# debugger.net
KiCad netlist of a schematic drawn in Altium Designer
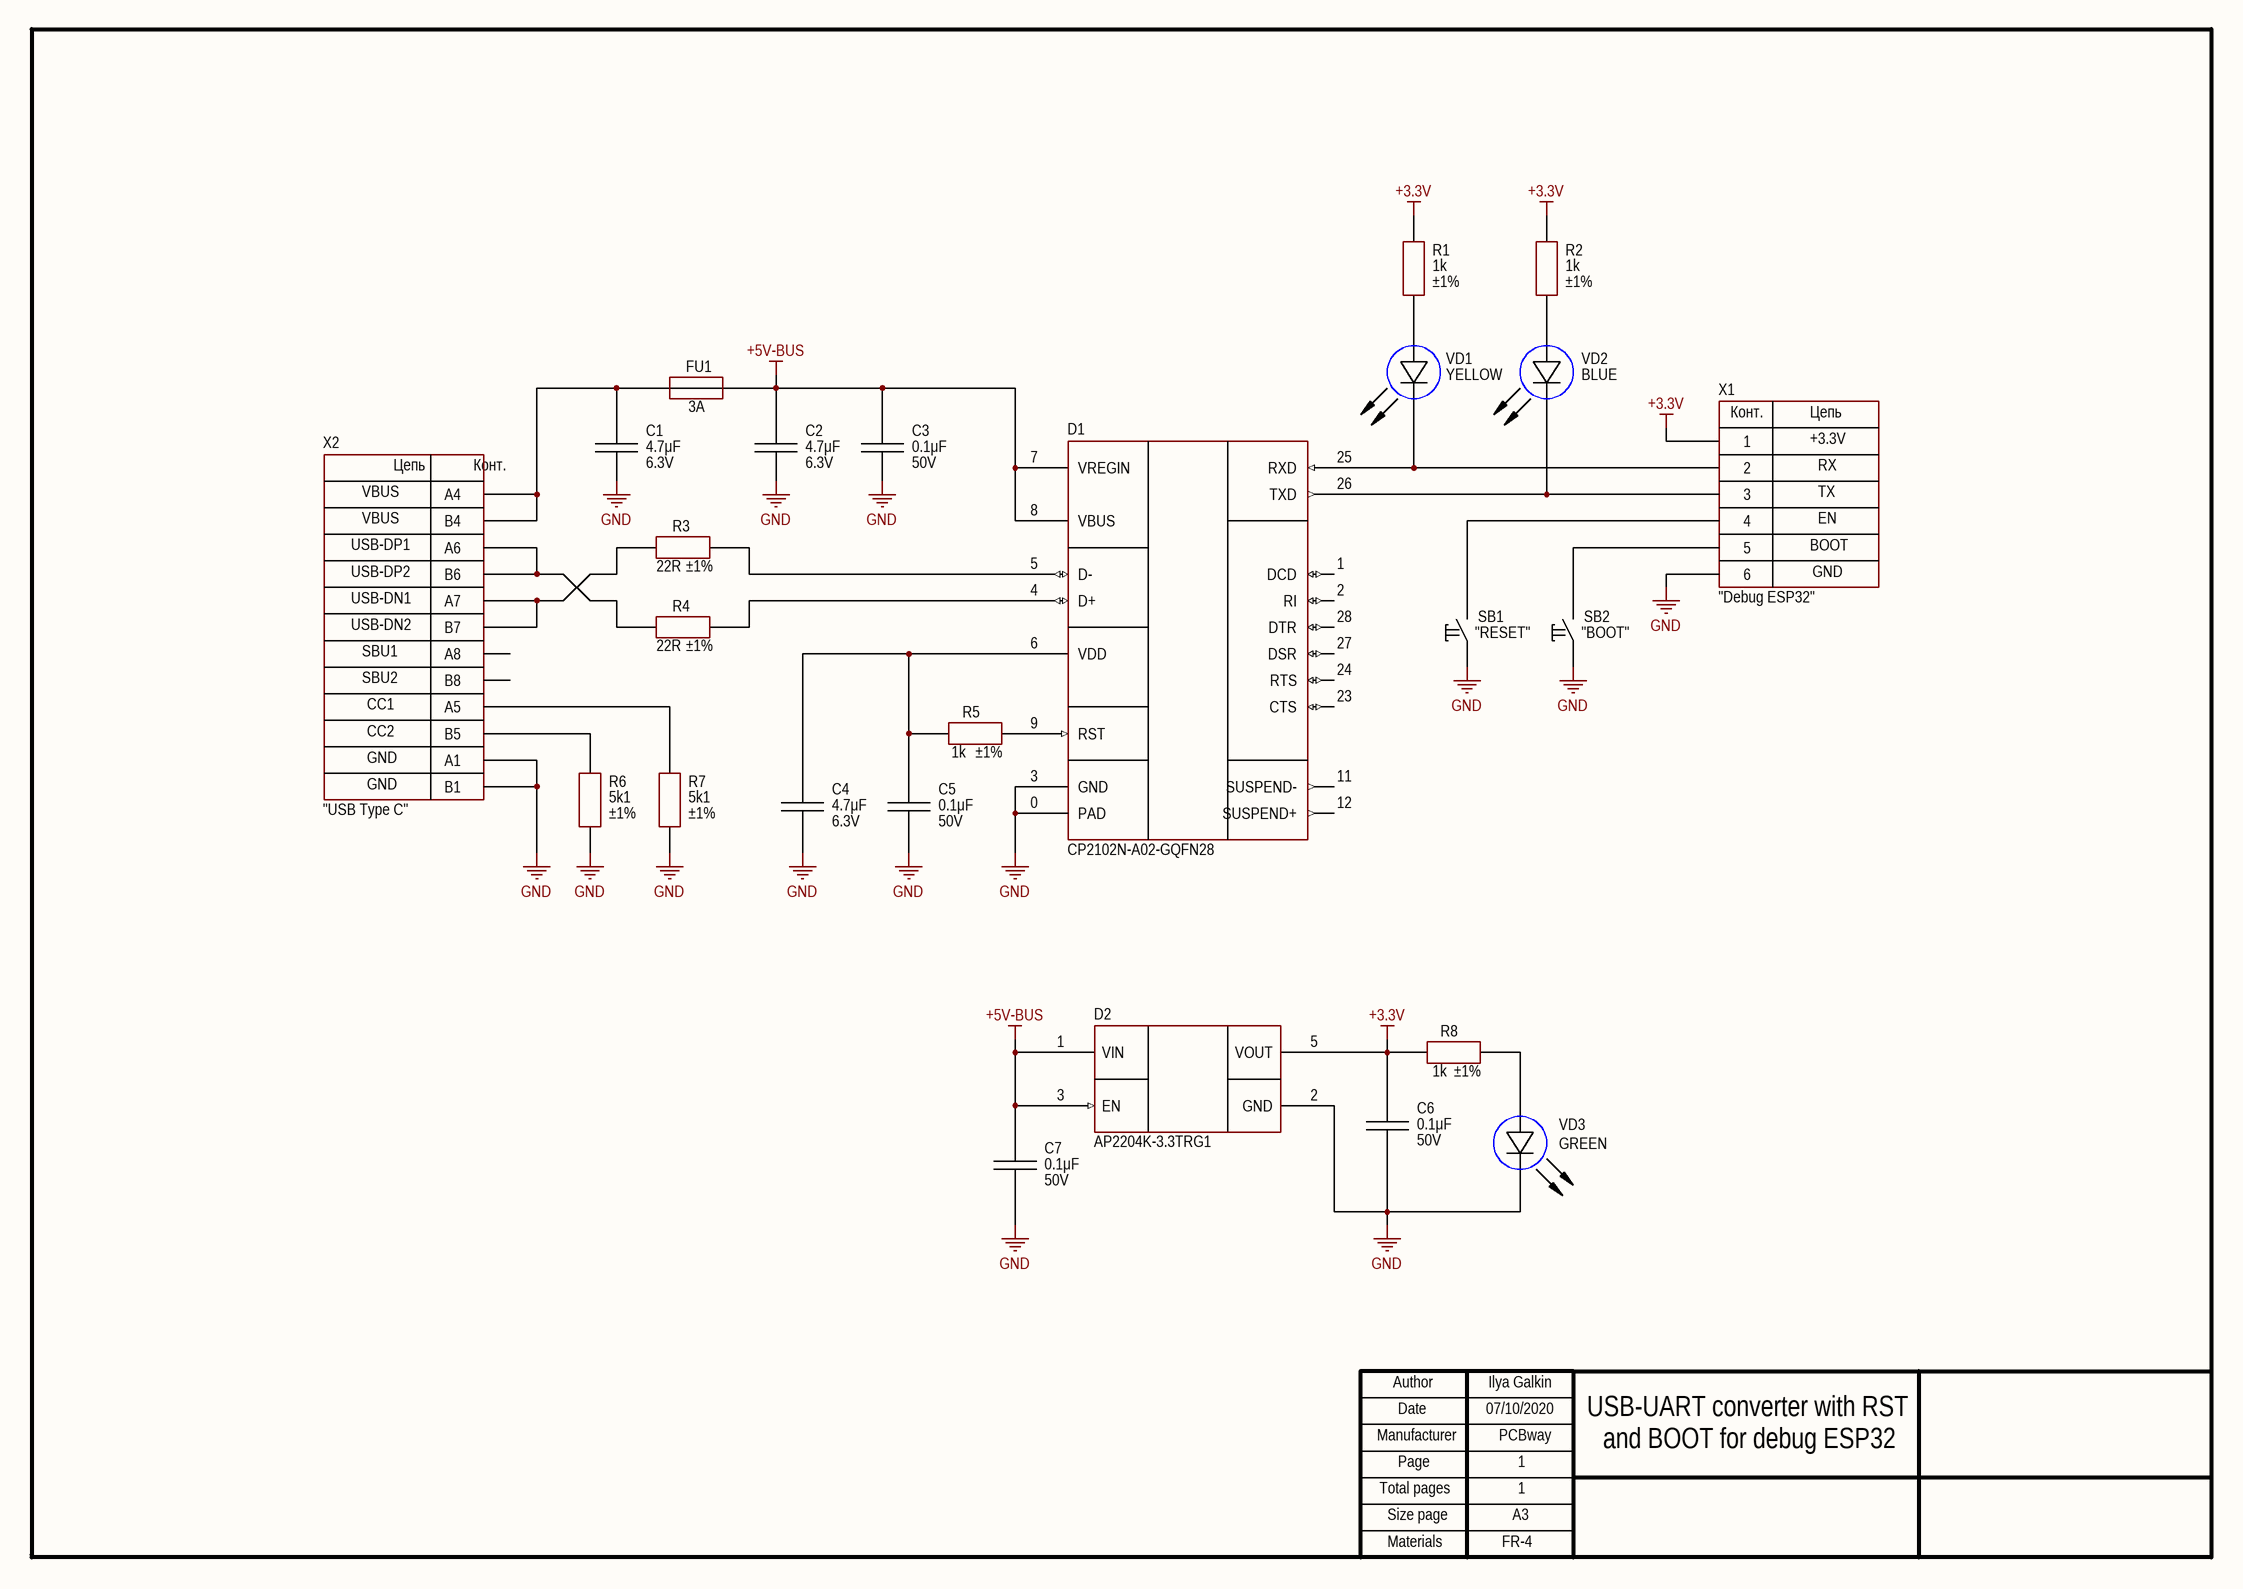
[diagram p0: debugger.SchDoc]

(export (version "E")
  (design (tool "Eeschema 10.0.6"))
  (components
    (comp (ref "C1")
      (value "4.7μF")
      (footprint "CAP: 0603")
      (fields
        (field (name "MANUFACTURER") "Samsung")
        (field (name "PARTNUMBER") "CL10B475KQ8NQNC")
        (field (name "VALUEMANUFACTURERPARTNUMBER") "Ceramic capacitor, 4.7μF, X7R, ±10%, 6.3V, 0603, -55...+125°C")
        (field (name "VOLTAGE") "6.3V")
      )
      (libsource (lib "capacitor") (part "Ceramic_0603"))
    )
    (comp (ref "C2")
      (value "4.7μF")
      (footprint "CAP: 0603")
      (fields
        (field (name "MANUFACTURER") "Samsung")
        (field (name "PARTNUMBER") "CL10B475KQ8NQNC")
        (field (name "VALUEMANUFACTURERPARTNUMBER") "Ceramic capacitor, 4.7μF, X7R, ±10%, 6.3V, 0603, -55...+125°C")
        (field (name "VOLTAGE") "6.3V")
      )
      (libsource (lib "capacitor") (part "Ceramic_0603"))
    )
    (comp (ref "C3")
      (value "0.1μF")
      (footprint "CAP: 0603")
      (fields
        (field (name "MANUFACTURER") "Samsung")
        (field (name "PARTNUMBER") "CL10B104KB8NNNL")
        (field (name "VALUEMANUFACTURERPARTNUMBER") "Ceramic capacitor, 0.1μF, X7R, ±10%, 50V, 0603, -55...+125°C")
        (field (name "VOLTAGE") "50V")
      )
      (libsource (lib "capacitor") (part "Ceramic_0603"))
    )
    (comp (ref "C4")
      (value "4.7μF")
      (footprint "CAP: 0603")
      (fields
        (field (name "MANUFACTURER") "Samsung")
        (field (name "PARTNUMBER") "CL10B475KQ8NQNC")
        (field (name "VALUEMANUFACTURERPARTNUMBER") "Ceramic capacitor, 4.7μF, X7R, ±10%, 6.3V, 0603, -55...+125°C")
        (field (name "VOLTAGE") "6.3V")
      )
      (libsource (lib "capacitor") (part "Ceramic_0603"))
    )
    (comp (ref "C5")
      (value "0.1μF")
      (footprint "CAP: 0603")
      (fields
        (field (name "MANUFACTURER") "Samsung")
        (field (name "PARTNUMBER") "CL10B104KB8NNNL")
        (field (name "VALUEMANUFACTURERPARTNUMBER") "Ceramic capacitor, 0.1μF, X7R, ±10%, 50V, 0603, -55...+125°C")
        (field (name "VOLTAGE") "50V")
      )
      (libsource (lib "capacitor") (part "Ceramic_0603"))
    )
    (comp (ref "C6")
      (value "0.1μF")
      (footprint "CAP: 0603")
      (fields
        (field (name "MANUFACTURER") "Samsung")
        (field (name "PARTNUMBER") "CL10B104KB8NNNL")
        (field (name "VALUEMANUFACTURERPARTNUMBER") "Ceramic capacitor, 0.1μF, X7R, ±10%, 50V, 0603, -55...+125°C")
        (field (name "VOLTAGE") "50V")
      )
      (libsource (lib "capacitor") (part "Ceramic_0603"))
    )
    (comp (ref "C7")
      (value "0.1μF")
      (footprint "CAP: 0603")
      (fields
        (field (name "MANUFACTURER") "Samsung")
        (field (name "PARTNUMBER") "CL10B104KB8NNNL")
        (field (name "VALUEMANUFACTURERPARTNUMBER") "Ceramic capacitor, 0.1μF, X7R, ±10%, 50V, 0603, -55...+125°C")
        (field (name "VOLTAGE") "50V")
      )
      (libsource (lib "capacitor") (part "Ceramic_0603"))
    )
    (comp (ref "D1")
      (value "~")
      (footprint "28-QFN (5x5)")
      (description "USB-to-UART")
      (fields
        (field (name "MANUFACTURER") "Silicon Labs")
        (field (name "VALUEMANUFACTURERPARTNUMBER") "IC usb-to-uart bridge, USB2.0, 3...3.6V, -40...+85°C, 28-VFQFN")
        (field (name "PARTNUMBER") "CP2102N-A02-GQFN28")
      )
      (libsource (lib "ic-interface") (part "CP2102N"))
    )
    (comp (ref "D2")
      (value "~")
      (footprint "SOT23-5")
      (description "Linear voltage regulator")
      (fields
        (field (name "MANUFACTURER") "Diodes Incorporated")
        (field (name "VALUEMANUFACTURERPARTNUMBER") "Linear voltage regulator, input 4...24V, 0.5V, output 3.3V, 0.15A, -40...+85°C, SOT23-6")
        (field (name "PARTNUMBER") "AP2204K-3.3TRG1")
      )
      (libsource (lib "ic-power-supply") (part "AP2204K-3.3TRG1"))
    )
    (comp (ref "FU1")
      (value "~")
      (footprint "FUSE: 1206")
      (fields
        (field (name "MANUFACTURER") "Panasonic")
        (field (name "VALUEMANUFACTURERPARTNUMBER") "Electromechanics relay, 32VDC, 3A, 1206 case, ")
        (field (name "PARTNUMBER") "ERB-RG3R00V")
        (field (name "MAXCURRENT") "3A")
      )
      (libsource (lib "electromechanics") (part "Fuse"))
    )
    (comp (ref "R1")
      (value "1k")
      (footprint "RES: 0603")
      (fields
        (field (name "MANUFACTURER") "Yageo")
        (field (name "PARTNUMBER") "RC0603FR-071KL")
        (field (name "VALUEMANUFACTURERPARTNUMBER") "Resistor film, 1k, ±1%, 0603, 0.1W, -55...+125°C")
        (field (name "TOLERANCE") "±1%")
      )
      (libsource (lib "") (part "Resistor_0603_1"))
    )
    (comp (ref "R2")
      (value "1k")
      (footprint "RES: 0603")
      (fields
        (field (name "MANUFACTURER") "Yageo")
        (field (name "PARTNUMBER") "RC0603FR-071KL")
        (field (name "VALUEMANUFACTURERPARTNUMBER") "Resistor film, 1k, ±1%, 0603, 0.1W, -55...+125°C")
        (field (name "TOLERANCE") "±1%")
      )
      (libsource (lib "") (part "Resistor_0603_1"))
    )
    (comp (ref "R3")
      (value "22R")
      (footprint "RES: 0603")
      (fields
        (field (name "MANUFACTURER") "Yageo")
        (field (name "PARTNUMBER") "RC0603FR-0722RL")
        (field (name "VALUEMANUFACTURERPARTNUMBER") "Resistor film, 22R, ±1%, 0603, 0.1W, -55...+125°C")
        (field (name "TOLERANCE") "±1%")
      )
      (libsource (lib "Resistor") (part "Resistor_0603"))
    )
    (comp (ref "R4")
      (value "22R")
      (footprint "RES: 0603")
      (fields
        (field (name "MANUFACTURER") "Yageo")
        (field (name "PARTNUMBER") "RC0603FR-0722RL")
        (field (name "VALUEMANUFACTURERPARTNUMBER") "Resistor film, 22R, ±1%, 0603, 0.1W, -55...+125°C")
        (field (name "TOLERANCE") "±1%")
      )
      (libsource (lib "Resistor") (part "Resistor_0603"))
    )
    (comp (ref "R5")
      (value "1k")
      (footprint "RES: 0603")
      (fields
        (field (name "MANUFACTURER") "Yageo")
        (field (name "PARTNUMBER") "RC0603FR-071KL")
        (field (name "VALUEMANUFACTURERPARTNUMBER") "Resistor film, 1k, ±1%, 0603, 0.1W, -55...+125°C")
        (field (name "TOLERANCE") "±1%")
      )
      (libsource (lib "resistor") (part "Resistor_0603"))
    )
    (comp (ref "R6")
      (value "5k1")
      (footprint "RES: 0603")
      (fields
        (field (name "MANUFACTURER") "Yageo")
        (field (name "PARTNUMBER") "RC0603FR-075K1L")
        (field (name "VALUEMANUFACTURERPARTNUMBER") "Resistor film, 5k1, ±1%, 0603, 0.1W, -55...+125°C")
        (field (name "TOLERANCE") "±1%")
      )
      (libsource (lib "") (part "Resistor_0603_1"))
    )
    (comp (ref "R7")
      (value "5k1")
      (footprint "RES: 0603")
      (fields
        (field (name "MANUFACTURER") "Yageo")
        (field (name "PARTNUMBER") "RC0603FR-075K1L")
        (field (name "VALUEMANUFACTURERPARTNUMBER") "Resistor film, 5k1, ±1%, 0603, 0.1W, -55...+125°C")
        (field (name "TOLERANCE") "±1%")
      )
      (libsource (lib "") (part "Resistor_0603_1"))
    )
    (comp (ref "R8")
      (value "1k")
      (footprint "RES: 0603")
      (fields
        (field (name "MANUFACTURER") "Yageo")
        (field (name "PARTNUMBER") "RC0603FR-071KL")
        (field (name "VALUEMANUFACTURERPARTNUMBER") "Resistor film, 1k, ±1%, 0603, 0.1W, -55...+125°C")
        (field (name "TOLERANCE") "±1%")
      )
      (libsource (lib "") (part "Resistor_0603_2"))
    )
    (comp (ref "SB1")
      (value "~")
      (footprint "BUT: 6x3.5 SMD")
      (fields
        (field (name "MANUFACTURER") "TE Connectivity")
        (field (name "VALUEMANUFACTURERPARTNUMBER") "Tactile button, 6x6mm")
        (field (name "PARTNUMBER") "FSM2JSMAATR")
        (field (name "COMMENTTEXT") "\"RESET\"")
      )
      (libsource (lib "electromechanics") (part "Button_tactile"))
    )
    (comp (ref "SB2")
      (value "~")
      (footprint "BUT: 6x3.5 SMD")
      (fields
        (field (name "MANUFACTURER") "TE Connectivity")
        (field (name "VALUEMANUFACTURERPARTNUMBER") "Tactile button, 6x3.5mm")
        (field (name "PARTNUMBER") "FSM2JSMAATR")
        (field (name "COMMENTTEXT") "\"BOOT\"")
      )
      (libsource (lib "electromechanics") (part "Button_tactile"))
    )
    (comp (ref "VD1")
      (value "~")
      (footprint "LED: 0603Y")
      (fields
        (field (name "MANUFACTURER") "Wurth")
        (field (name "VALUEMANUFACTURERPARTNUMBER") "LED, 20mA, 2V, 0603, -55...+150°C")
        (field (name "PARTNUMBER") "150060YS75000")
        (field (name "COLOR") "YELLOW")
      )
      (libsource (lib "Diode") (part "LED_single"))
    )
    (comp (ref "VD2")
      (value "~")
      (footprint "LED: 0603B")
      (fields
        (field (name "MANUFACTURER") "Wurth")
        (field (name "VALUEMANUFACTURERPARTNUMBER") "LED, 20mA, 3.2V, 0603, -55...+150°C")
        (field (name "PARTNUMBER") "150060BS75000")
        (field (name "COLOR") "BLUE")
      )
      (libsource (lib "Diode") (part "LED_single"))
    )
    (comp (ref "VD3")
      (value "~")
      (footprint "LED: 0603G")
      (fields
        (field (name "MANUFACTURER") "Wurth")
        (field (name "VALUEMANUFACTURERPARTNUMBER") "LED, 20mA, 2V, 0603, -55...+150°C")
        (field (name "PARTNUMBER") "150060VS75000")
        (field (name "COLOR") "GREEN")
      )
      (libsource (lib "Diode") (part "LED_single"))
    )
    (comp (ref "X1")
      (value "~")
      (footprint "CON: SM06B-GHS")
      (fields
        (field (name "MANUFACTURER") "JST")
        (field (name "VALUEMANUFACTURERPARTNUMBER") "Connector, 6pin, 1.25mm, 50VDC, 1A")
        (field (name "PARTNUMBER") "SM06B-GHS")
        (field (name "COMMENTTEXT") "\"Debug ESP32\"")
      )
      (libsource (lib "connector") (part "Connector_SM06B"))
    )
    (comp (ref "X2")
      (value "~")
      (footprint "CON: TYPE-C-31-M-12")
      (fields
        (field (name "MANUFACTURER") "Korean Hroparts")
        (field (name "VALUEMANUFACTURERPARTNUMBER") "USB Type C, 3A")
        (field (name "PARTNUMBER") "TYPE-C-31-M-12")
        (field (name "COMMENTTEXT") "\"USB Type C\"")
      )
      (libsource (lib "connector") (part "Connector_USB_Type_C"))
    )
  )
  (nets
    (net (code "1") (name "+3.3V") (class "Default")
      (node (ref "C6") (pin "2") (pinfunction "2_2") (pintype "passive"))
      (node (ref "D2") (pin "5") (pinfunction "VOUT_5") (pintype "passive"))
      (node (ref "R1") (pin "2") (pinfunction "2_2") (pintype "passive"))
      (node (ref "R2") (pin "2") (pinfunction "2_2") (pintype "passive"))
      (node (ref "R8") (pin "2") (pinfunction "2_2") (pintype "passive"))
      (node (ref "X1") (pin "1") (pinfunction "1_1") (pintype "passive"))
    )
    (net (code "2") (name "+5V-BUS") (class "Default")
      (node (ref "C2") (pin "2") (pinfunction "2_2") (pintype "passive"))
      (node (ref "C3") (pin "2") (pinfunction "2_2") (pintype "passive"))
      (node (ref "C7") (pin "2") (pinfunction "2_2") (pintype "passive"))
      (node (ref "D1") (pin "7") (pinfunction "VREGIN_7") (pintype "passive"))
      (node (ref "D1") (pin "8") (pinfunction "VBUS_8") (pintype "passive"))
      (node (ref "D2") (pin "1") (pinfunction "VIN_1") (pintype "passive"))
      (node (ref "D2") (pin "3") (pinfunction "EN_3") (pintype "input"))
      (node (ref "FU1") (pin "2") (pinfunction "2_2") (pintype "passive"))
    )
    (net (code "3") (name "GND") (class "Default")
      (node (ref "C1") (pin "1") (pinfunction "1_1") (pintype "passive"))
      (node (ref "C2") (pin "1") (pinfunction "1_1") (pintype "passive"))
      (node (ref "C3") (pin "1") (pinfunction "1_1") (pintype "passive"))
      (node (ref "C4") (pin "1") (pinfunction "1_1") (pintype "passive"))
      (node (ref "C5") (pin "1") (pinfunction "1_1") (pintype "passive"))
      (node (ref "C6") (pin "1") (pinfunction "1_1") (pintype "passive"))
      (node (ref "C7") (pin "1") (pinfunction "1_1") (pintype "passive"))
      (node (ref "D1") (pin "0") (pinfunction "PAD_0") (pintype "passive"))
      (node (ref "D1") (pin "3") (pinfunction "GND_3") (pintype "passive"))
      (node (ref "D2") (pin "2") (pinfunction "GND_2") (pintype "passive"))
      (node (ref "R6") (pin "1") (pinfunction "1_1") (pintype "passive"))
      (node (ref "R7") (pin "1") (pinfunction "1_1") (pintype "passive"))
      (node (ref "SB1") (pin "1") (pinfunction "1_1") (pintype "passive"))
      (node (ref "SB2") (pin "1") (pinfunction "1_1") (pintype "passive"))
      (node (ref "VD3") (pin "2") (pinfunction "C_2") (pintype "passive"))
      (node (ref "X1") (pin "6") (pinfunction "6_6") (pintype "power_in"))
      (node (ref "X2") (pin "A1") (pinfunction "A1_A1") (pintype "power_in"))
      (node (ref "X2") (pin "B1") (pinfunction "B1_B1") (pintype "power_in"))
    )
    (net (code "4") (name "Net-(C1-Pad2)") (class "Default")
      (node (ref "C1") (pin "2") (pinfunction "2_2") (pintype "passive"))
      (node (ref "FU1") (pin "1") (pinfunction "1_1") (pintype "passive"))
      (node (ref "X2") (pin "A4") (pinfunction "A4_A4") (pintype "passive"))
      (node (ref "X2") (pin "B4") (pinfunction "B4_B4") (pintype "passive"))
    )
    (net (code "5") (name "Net-(D1-D+)") (class "Default")
      (node (ref "D1") (pin "4") (pinfunction "D+_4") (pintype "bidirectional"))
      (node (ref "R4") (pin "1") (pinfunction "1_1") (pintype "passive"))
    )
    (net (code "6") (name "Net-(D1-D-)") (class "Default")
      (node (ref "D1") (pin "5") (pinfunction "D-_5") (pintype "bidirectional"))
      (node (ref "R3") (pin "1") (pinfunction "1_1") (pintype "passive"))
    )
    (net (code "7") (name "Net-(D1-RST)") (class "Default")
      (node (ref "D1") (pin "9") (pinfunction "RST_9") (pintype "input"))
      (node (ref "R5") (pin "2") (pinfunction "2_2") (pintype "passive"))
    )
    (net (code "8") (name "Net-(D1-RXD)") (class "Default")
      (node (ref "D1") (pin "25") (pinfunction "RXD_25") (pintype "input"))
      (node (ref "VD1") (pin "2") (pinfunction "C_2") (pintype "passive"))
      (node (ref "X1") (pin "2") (pinfunction "2_2") (pintype "passive"))
    )
    (net (code "9") (name "Net-(D1-TXD)") (class "Default")
      (node (ref "D1") (pin "26") (pinfunction "TXD_26") (pintype "output"))
      (node (ref "VD2") (pin "2") (pinfunction "C_2") (pintype "passive"))
      (node (ref "X1") (pin "3") (pinfunction "3_3") (pintype "power_in"))
    )
    (net (code "10") (name "Net-(D1-VDD)") (class "Default")
      (node (ref "C4") (pin "2") (pinfunction "2_2") (pintype "passive"))
      (node (ref "C5") (pin "2") (pinfunction "2_2") (pintype "passive"))
      (node (ref "D1") (pin "6") (pinfunction "VDD_6") (pintype "passive"))
      (node (ref "R5") (pin "1") (pinfunction "1_1") (pintype "passive"))
    )
    (net (code "11") (name "Net-(R3-Pad2)") (class "Default")
      (node (ref "R3") (pin "2") (pinfunction "2_2") (pintype "passive"))
      (node (ref "X2") (pin "A7") (pinfunction "A7_A7") (pintype "power_in"))
      (node (ref "X2") (pin "B7") (pinfunction "B7_B7") (pintype "power_in"))
    )
    (net (code "12") (name "Net-(R4-Pad2)") (class "Default")
      (node (ref "R4") (pin "2") (pinfunction "2_2") (pintype "passive"))
      (node (ref "X2") (pin "A6") (pinfunction "A6_A6") (pintype "power_in"))
      (node (ref "X2") (pin "B6") (pinfunction "B6_B6") (pintype "power_in"))
    )
    (net (code "13") (name "Net-(R6-Pad2)") (class "Default")
      (node (ref "R6") (pin "2") (pinfunction "2_2") (pintype "passive"))
      (node (ref "X2") (pin "B5") (pinfunction "B5_B5") (pintype "power_in"))
    )
    (net (code "14") (name "Net-(R7-Pad2)") (class "Default")
      (node (ref "R7") (pin "2") (pinfunction "2_2") (pintype "passive"))
      (node (ref "X2") (pin "A5") (pinfunction "A5_A5") (pintype "power_in"))
    )
    (net (code "15") (name "Net-(SB1-Pad2)") (class "Default")
      (node (ref "SB1") (pin "2") (pinfunction "2_2") (pintype "passive"))
      (node (ref "X1") (pin "4") (pinfunction "4_4") (pintype "power_in"))
    )
    (net (code "16") (name "Net-(SB2-Pad2)") (class "Default")
      (node (ref "SB2") (pin "2") (pinfunction "2_2") (pintype "passive"))
      (node (ref "X1") (pin "5") (pinfunction "5_5") (pintype "power_in"))
    )
    (net (code "17") (name "Net-(VD1-A)") (class "Default")
      (node (ref "R1") (pin "1") (pinfunction "1_1") (pintype "passive"))
      (node (ref "VD1") (pin "1") (pinfunction "A_1") (pintype "passive"))
    )
    (net (code "18") (name "Net-(VD2-A)") (class "Default")
      (node (ref "R2") (pin "1") (pinfunction "1_1") (pintype "passive"))
      (node (ref "VD2") (pin "1") (pinfunction "A_1") (pintype "passive"))
    )
    (net (code "19") (name "Net-(VD3-A)") (class "Default")
      (node (ref "R8") (pin "1") (pinfunction "1_1") (pintype "passive"))
      (node (ref "VD3") (pin "1") (pinfunction "A_1") (pintype "passive"))
    )
    (net (code "20") (name "unconnected-(D1-CTS-Pad23)") (class "Default")
      (node (ref "D1") (pin "23") (pinfunction "CTS_23") (pintype "bidirectional"))
    )
    (net (code "21") (name "unconnected-(D1-DCD-Pad1)") (class "Default")
      (node (ref "D1") (pin "1") (pinfunction "DCD_1") (pintype "bidirectional"))
    )
    (net (code "22") (name "unconnected-(D1-DSR-Pad27)") (class "Default")
      (node (ref "D1") (pin "27") (pinfunction "DSR_27") (pintype "bidirectional"))
    )
    (net (code "23") (name "unconnected-(D1-DTR-Pad28)") (class "Default")
      (node (ref "D1") (pin "28") (pinfunction "DTR_28") (pintype "bidirectional"))
    )
    (net (code "24") (name "unconnected-(D1-RI-Pad2)") (class "Default")
      (node (ref "D1") (pin "2") (pinfunction "RI_2") (pintype "bidirectional"))
    )
    (net (code "25") (name "unconnected-(D1-RTS-Pad24)") (class "Default")
      (node (ref "D1") (pin "24") (pinfunction "RTS_24") (pintype "bidirectional"))
    )
    (net (code "26") (name "unconnected-(D1-SUSPEND+-Pad12)") (class "Default")
      (node (ref "D1") (pin "12") (pinfunction "SUSPEND+_12") (pintype "output"))
    )
    (net (code "27") (name "unconnected-(D1-SUSPEND--Pad11)") (class "Default")
      (node (ref "D1") (pin "11") (pinfunction "SUSPEND-_11") (pintype "output"))
    )
    (net (code "28") (name "unconnected-(X2-PadA8)") (class "Default")
      (node (ref "X2") (pin "A8") (pinfunction "A8_A8") (pintype "power_in"))
    )
    (net (code "29") (name "unconnected-(X2-PadB8)") (class "Default")
      (node (ref "X2") (pin "B8") (pinfunction "B8_B8") (pintype "power_in"))
    )
  )
)
